# untitled.net
KiCad netlist of a schematic drawn in EAGLE
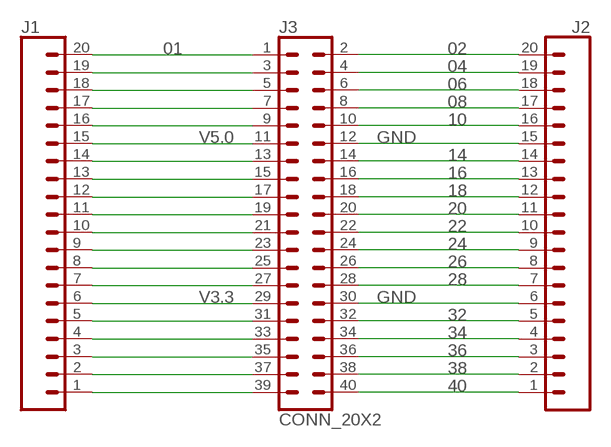
[diagram p0: schematic, sheet 1]

(export (version "E")
  (design (tool "Eeschema 10.0.6"))
  (components
    (comp (ref "J1")
      (value "CONN_20")
      (footprint "eagle-import:1X20")
      (libsource (lib "eagle-import") (part "CONN_20"))
    )
    (comp (ref "J2")
      (value "CONN_20")
      (footprint "eagle-import:1X20")
      (libsource (lib "eagle-import") (part "CONN_20"))
    )
    (comp (ref "J3")
      (value "CONN_20X2")
      (footprint "eagle-import:2X20")
      (libsource (lib "eagle-import") (part "CONN_20X2"))
    )
  )
  (nets
    (net (code "1") (name "/01") (class "Default")
      (node (ref "J1") (pin "20") (pinfunction "20_20") (pintype "passive"))
      (node (ref "J3") (pin "1") (pinfunction "1_1") (pintype "passive"))
    )
    (net (code "2") (name "/02") (class "Default")
      (node (ref "J2") (pin "20") (pinfunction "20_20") (pintype "passive"))
      (node (ref "J3") (pin "2") (pinfunction "2_2") (pintype "passive"))
    )
    (net (code "3") (name "/04") (class "Default")
      (node (ref "J2") (pin "19") (pinfunction "19_19") (pintype "passive"))
      (node (ref "J3") (pin "4") (pinfunction "4_4") (pintype "passive"))
    )
    (net (code "4") (name "/06") (class "Default")
      (node (ref "J2") (pin "18") (pinfunction "18_18") (pintype "passive"))
      (node (ref "J3") (pin "6") (pinfunction "6_6") (pintype "passive"))
    )
    (net (code "5") (name "/08") (class "Default")
      (node (ref "J2") (pin "17") (pinfunction "17_17") (pintype "passive"))
      (node (ref "J3") (pin "8") (pinfunction "8_8") (pintype "passive"))
    )
    (net (code "6") (name "/10") (class "Default")
      (node (ref "J2") (pin "16") (pinfunction "16_16") (pintype "passive"))
      (node (ref "J3") (pin "10") (pinfunction "10_10") (pintype "passive"))
    )
    (net (code "7") (name "/14") (class "Default")
      (node (ref "J2") (pin "14") (pinfunction "14_14") (pintype "passive"))
      (node (ref "J3") (pin "14") (pinfunction "14_14") (pintype "passive"))
    )
    (net (code "8") (name "/16") (class "Default")
      (node (ref "J2") (pin "13") (pinfunction "13_13") (pintype "passive"))
      (node (ref "J3") (pin "16") (pinfunction "16_16") (pintype "passive"))
    )
    (net (code "9") (name "/18") (class "Default")
      (node (ref "J2") (pin "12") (pinfunction "12_12") (pintype "passive"))
      (node (ref "J3") (pin "18") (pinfunction "18_18") (pintype "passive"))
    )
    (net (code "10") (name "/20") (class "Default")
      (node (ref "J2") (pin "11") (pinfunction "11_11") (pintype "passive"))
      (node (ref "J3") (pin "20") (pinfunction "20_20") (pintype "passive"))
    )
    (net (code "11") (name "/22") (class "Default")
      (node (ref "J2") (pin "10") (pinfunction "10_10") (pintype "passive"))
      (node (ref "J3") (pin "22") (pinfunction "22_22") (pintype "passive"))
    )
    (net (code "12") (name "/24") (class "Default")
      (node (ref "J2") (pin "9") (pinfunction "9_9") (pintype "passive"))
      (node (ref "J3") (pin "24") (pinfunction "24_24") (pintype "passive"))
    )
    (net (code "13") (name "/26") (class "Default")
      (node (ref "J2") (pin "8") (pinfunction "8_8") (pintype "passive"))
      (node (ref "J3") (pin "26") (pinfunction "26_26") (pintype "passive"))
    )
    (net (code "14") (name "/28") (class "Default")
      (node (ref "J2") (pin "7") (pinfunction "7_7") (pintype "passive"))
      (node (ref "J3") (pin "28") (pinfunction "28_28") (pintype "passive"))
    )
    (net (code "15") (name "/32") (class "Default")
      (node (ref "J2") (pin "5") (pinfunction "5_5") (pintype "passive"))
      (node (ref "J3") (pin "32") (pinfunction "32_32") (pintype "passive"))
    )
    (net (code "16") (name "/34") (class "Default")
      (node (ref "J2") (pin "4") (pinfunction "4_4") (pintype "passive"))
      (node (ref "J3") (pin "34") (pinfunction "34_34") (pintype "passive"))
    )
    (net (code "17") (name "/36") (class "Default")
      (node (ref "J2") (pin "3") (pinfunction "3_3") (pintype "passive"))
      (node (ref "J3") (pin "36") (pinfunction "36_36") (pintype "passive"))
    )
    (net (code "18") (name "/38") (class "Default")
      (node (ref "J2") (pin "2") (pinfunction "2_2") (pintype "passive"))
      (node (ref "J3") (pin "38") (pinfunction "38_38") (pintype "passive"))
    )
    (net (code "19") (name "/40") (class "Default")
      (node (ref "J2") (pin "1") (pinfunction "1_1") (pintype "passive"))
      (node (ref "J3") (pin "40") (pinfunction "40_40") (pintype "passive"))
    )
    (net (code "20") (name "/GND") (class "Default")
      (node (ref "J2") (pin "15") (pinfunction "15_15") (pintype "passive"))
      (node (ref "J2") (pin "6") (pinfunction "6_6") (pintype "passive"))
      (node (ref "J3") (pin "12") (pinfunction "12_12") (pintype "passive"))
      (node (ref "J3") (pin "30") (pinfunction "30_30") (pintype "passive"))
    )
    (net (code "21") (name "/V3.3") (class "Default")
      (node (ref "J1") (pin "6") (pinfunction "6_6") (pintype "passive"))
      (node (ref "J3") (pin "29") (pinfunction "29_29") (pintype "passive"))
    )
    (net (code "22") (name "/V5.0") (class "Default")
      (node (ref "J1") (pin "15") (pinfunction "15_15") (pintype "passive"))
      (node (ref "J3") (pin "11") (pinfunction "11_11") (pintype "passive"))
    )
    (net (code "23") (name "Net-(J1-Pad1)") (class "Default")
      (node (ref "J1") (pin "1") (pinfunction "1_1") (pintype "passive"))
      (node (ref "J3") (pin "39") (pinfunction "39_39") (pintype "passive"))
    )
    (net (code "24") (name "Net-(J1-Pad2)") (class "Default")
      (node (ref "J1") (pin "2") (pinfunction "2_2") (pintype "passive"))
      (node (ref "J3") (pin "37") (pinfunction "37_37") (pintype "passive"))
    )
    (net (code "25") (name "Net-(J1-Pad3)") (class "Default")
      (node (ref "J1") (pin "3") (pinfunction "3_3") (pintype "passive"))
      (node (ref "J3") (pin "35") (pinfunction "35_35") (pintype "passive"))
    )
    (net (code "26") (name "Net-(J1-Pad4)") (class "Default")
      (node (ref "J1") (pin "4") (pinfunction "4_4") (pintype "passive"))
      (node (ref "J3") (pin "33") (pinfunction "33_33") (pintype "passive"))
    )
    (net (code "27") (name "Net-(J1-Pad5)") (class "Default")
      (node (ref "J1") (pin "5") (pinfunction "5_5") (pintype "passive"))
      (node (ref "J3") (pin "31") (pinfunction "31_31") (pintype "passive"))
    )
    (net (code "28") (name "Net-(J1-Pad7)") (class "Default")
      (node (ref "J1") (pin "7") (pinfunction "7_7") (pintype "passive"))
      (node (ref "J3") (pin "27") (pinfunction "27_27") (pintype "passive"))
    )
    (net (code "29") (name "Net-(J1-Pad8)") (class "Default")
      (node (ref "J1") (pin "8") (pinfunction "8_8") (pintype "passive"))
      (node (ref "J3") (pin "25") (pinfunction "25_25") (pintype "passive"))
    )
    (net (code "30") (name "Net-(J1-Pad9)") (class "Default")
      (node (ref "J1") (pin "9") (pinfunction "9_9") (pintype "passive"))
      (node (ref "J3") (pin "23") (pinfunction "23_23") (pintype "passive"))
    )
    (net (code "31") (name "Net-(J1-Pad10)") (class "Default")
      (node (ref "J1") (pin "10") (pinfunction "10_10") (pintype "passive"))
      (node (ref "J3") (pin "21") (pinfunction "21_21") (pintype "passive"))
    )
    (net (code "32") (name "Net-(J1-Pad11)") (class "Default")
      (node (ref "J1") (pin "11") (pinfunction "11_11") (pintype "passive"))
      (node (ref "J3") (pin "19") (pinfunction "19_19") (pintype "passive"))
    )
    (net (code "33") (name "Net-(J1-Pad12)") (class "Default")
      (node (ref "J1") (pin "12") (pinfunction "12_12") (pintype "passive"))
      (node (ref "J3") (pin "17") (pinfunction "17_17") (pintype "passive"))
    )
    (net (code "34") (name "Net-(J1-Pad13)") (class "Default")
      (node (ref "J1") (pin "13") (pinfunction "13_13") (pintype "passive"))
      (node (ref "J3") (pin "15") (pinfunction "15_15") (pintype "passive"))
    )
    (net (code "35") (name "Net-(J1-Pad14)") (class "Default")
      (node (ref "J1") (pin "14") (pinfunction "14_14") (pintype "passive"))
      (node (ref "J3") (pin "13") (pinfunction "13_13") (pintype "passive"))
    )
    (net (code "36") (name "Net-(J1-Pad16)") (class "Default")
      (node (ref "J1") (pin "16") (pinfunction "16_16") (pintype "passive"))
      (node (ref "J3") (pin "9") (pinfunction "9_9") (pintype "passive"))
    )
    (net (code "37") (name "Net-(J1-Pad17)") (class "Default")
      (node (ref "J1") (pin "17") (pinfunction "17_17") (pintype "passive"))
      (node (ref "J3") (pin "7") (pinfunction "7_7") (pintype "passive"))
    )
    (net (code "38") (name "Net-(J1-Pad18)") (class "Default")
      (node (ref "J1") (pin "18") (pinfunction "18_18") (pintype "passive"))
      (node (ref "J3") (pin "5") (pinfunction "5_5") (pintype "passive"))
    )
    (net (code "39") (name "Net-(J1-Pad19)") (class "Default")
      (node (ref "J1") (pin "19") (pinfunction "19_19") (pintype "passive"))
      (node (ref "J3") (pin "3") (pinfunction "3_3") (pintype "passive"))
    )
  )
)
